# Power.net
KiCad netlist of a schematic drawn in Altium Designer
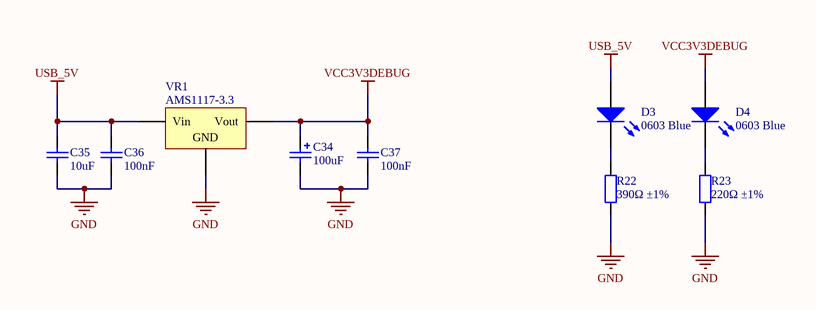
[diagram p0: Power.SchDoc]

(export (version "E")
  (design (tool "Eeschema 10.0.6"))
  (components
    (comp (ref "C34")
      (value "100uF")
      (footprint "CASE-B_3528")
      (description "Tantalum capacitor")
      (fields (field (name "MANUFACTURER") "AVX") (field (name "PARTNUMBER") "TAJB107K006RNJ"))
      (libsource (lib "Cap") (part "3528 100uF (107) 10% 6.3V"))
    )
    (comp (ref "C35")
      (value "10uF")
      (footprint "1206_C")
      (description "Chip capacitors")
      (fields
        (field (name "MANUFACTURER") "Samsung Electro-Mechanics")
        (field (name "PARTNUMBER") "CL31A106KBHNNNE")
      )
      (libsource (lib "Cap") (part "1206 10uF (106) 10% 50V"))
    )
    (comp (ref "C36")
      (value "100nF")
      (footprint "0402_C")
      (description "Chip capacitors")
      (fields
        (field (name "MANUFACTURER") "Samsung Electro-Mechanics")
        (field (name "PARTNUMBER") "CL05B104KO5NNNC")
      )
      (libsource (lib "Miscellaneous Devices LC") (part "0402 100nF (104) 10% 16V"))
    )
    (comp (ref "C37")
      (value "100nF")
      (footprint "1206_C")
      (description "Chip capacitors")
      (fields
        (field (name "MANUFACTURER") "Samsung Electro-Mechanics")
        (field (name "PARTNUMBER") "CL31B104KBCNNNC")
      )
      (libsource (lib "Miscellaneous Devices LC") (part "1206 100nF (104) 10% 50V"))
    )
    (comp (ref "D3")
      (value "0603 Blue")
      (footprint "0603_LED_S1")
      (description "LED")
      (libsource (lib "Miscellaneous Devices LC") (part "0603 LED Blue"))
    )
    (comp (ref "D4")
      (value "0603 Blue")
      (footprint "0603_LED_S1")
      (description "LED")
      (libsource (lib "Miscellaneous Devices LC") (part "0603 LED Blue"))
    )
    (comp (ref "R22")
      (value "390Ω ±1%")
      (footprint "0603_R")
      (description "Chip resistor")
      (fields (field (name "MANUFACTURER") "Uniroyal Elec") (field (name "PARTNUMBER") "0603WAF3900T5E"))
      (libsource (lib "RES") (part "0603 390R (3900) 1%"))
    )
    (comp (ref "R23")
      (value "220Ω ±1%")
      (footprint "0402_R")
      (description "Chip resistor")
      (fields (field (name "MANUFACTURER") "Uniroyal Elec") (field (name "PARTNUMBER") "0402WGF2200TCE"))
      (libsource (lib "RES") (part "0402 220R (2200) 1%"))
    )
    (comp (ref "VR1")
      (value "AMS1117-3.3")
      (footprint "SOT-223")
      (description "低压差线性稳压(LDO)")
      (libsource (lib "Miscellaneous Devices LC") (part "SOT-223 AMS1117-3.3"))
    )
  )
  (nets
    (net (code "1") (name "GND") (class "Default")
      (node (ref "C34") (pin "2") (pinfunction "2_2") (pintype "passive"))
      (node (ref "C35") (pin "1") (pinfunction "1_1") (pintype "passive"))
      (node (ref "C36") (pin "1") (pinfunction "1_1") (pintype "passive"))
      (node (ref "C37") (pin "1") (pinfunction "1_1") (pintype "passive"))
      (node (ref "R22") (pin "1") (pinfunction "1_1") (pintype "passive"))
      (node (ref "R23") (pin "1") (pinfunction "1_1") (pintype "passive"))
      (node (ref "VR1") (pin "1") (pinfunction "GND_1") (pintype "passive"))
    )
    (net (code "2") (name "Net-(D3-PadK)") (class "Default")
      (node (ref "D3") (pin "K") (pinfunction "K_K") (pintype "passive"))
      (node (ref "R22") (pin "2") (pinfunction "2_2") (pintype "passive"))
    )
    (net (code "3") (name "Net-(D4-PadK)") (class "Default")
      (node (ref "D4") (pin "K") (pinfunction "K_K") (pintype "passive"))
      (node (ref "R23") (pin "2") (pinfunction "2_2") (pintype "passive"))
    )
    (net (code "4") (name "USB_5V") (class "Default")
      (node (ref "C35") (pin "2") (pinfunction "2_2") (pintype "passive"))
      (node (ref "C36") (pin "2") (pinfunction "2_2") (pintype "passive"))
      (node (ref "D3") (pin "A") (pinfunction "A_A") (pintype "passive"))
      (node (ref "VR1") (pin "3") (pinfunction "Vin_3") (pintype "passive"))
    )
    (net (code "5") (name "VCC3V3DEBUG") (class "Default")
      (node (ref "C34") (pin "1") (pinfunction "1_1") (pintype "passive"))
      (node (ref "C37") (pin "2") (pinfunction "2_2") (pintype "passive"))
      (node (ref "D4") (pin "A") (pinfunction "A_A") (pintype "passive"))
      (node (ref "VR1") (pin "2") (pinfunction "Vout_2") (pintype "passive"))
    )
  )
)
